# mrf89_v0_1.net
KiCad netlist of a schematic drawn in EAGLE
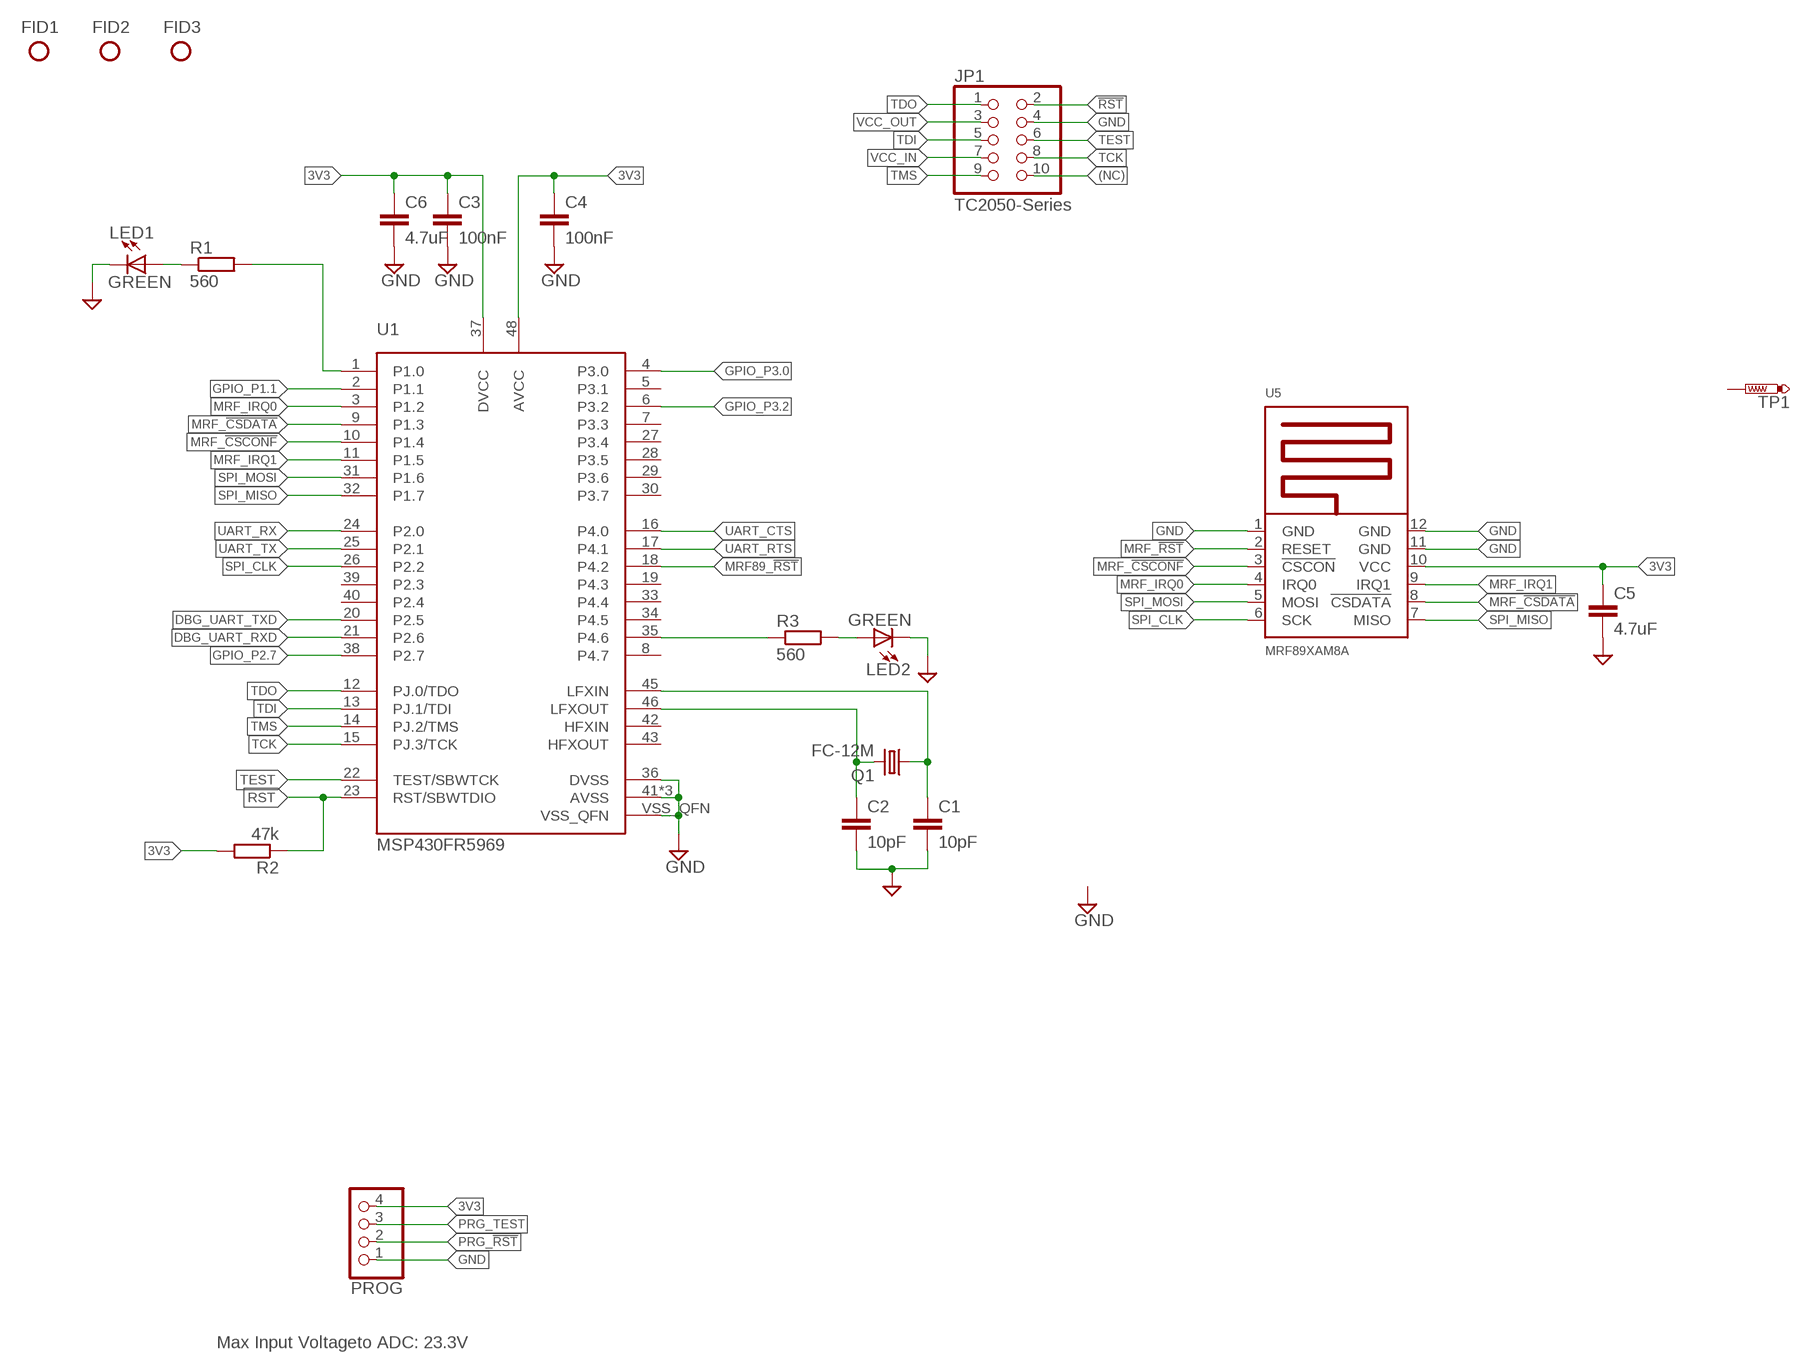
[diagram p0: schematic, sheet 1]

(export (version "E")
  (design (tool "Eeschema 10.0.6"))
  (components
    (comp (ref "C1")
      (value "10pF")
      (footprint "eagle-import:C0603")
      (libsource (lib "eagle-import") (part "C-EUC0603"))
    )
    (comp (ref "C2")
      (value "10pF")
      (footprint "eagle-import:C0603")
      (libsource (lib "eagle-import") (part "C-EUC0603"))
    )
    (comp (ref "C3")
      (value "100nF")
      (footprint "eagle-import:C0603")
      (libsource (lib "eagle-import") (part "C-EUC0603"))
    )
    (comp (ref "C4")
      (value "100nF")
      (footprint "eagle-import:C0603")
      (libsource (lib "eagle-import") (part "C-EUC0603"))
    )
    (comp (ref "C5")
      (value "4.7uF")
      (footprint "eagle-import:C0805")
      (libsource (lib "eagle-import") (part "C-EUC0805"))
    )
    (comp (ref "C6")
      (value "4.7uF")
      (footprint "eagle-import:C0805")
      (libsource (lib "eagle-import") (part "C-EUC0805"))
    )
    (comp (ref "FID1")
      (value "FIDUCIAL")
      (footprint "eagle-import:FIDUCIAL")
      (libsource (lib "eagle-import") (part "FIDUCIAL"))
    )
    (comp (ref "FID2")
      (value "FIDUCIAL")
      (footprint "eagle-import:FIDUCIAL")
      (libsource (lib "eagle-import") (part "FIDUCIAL"))
    )
    (comp (ref "FID3")
      (value "FIDUCIAL")
      (footprint "eagle-import:FIDUCIAL")
      (libsource (lib "eagle-import") (part "FIDUCIAL"))
    )
    (comp (ref "JP1")
      (value "TC2050-Series")
      (footprint "eagle-import:2X05")
      (libsource (lib "eagle-import") (part "PINHD-2X5"))
    )
    (comp (ref "LED1")
      (value "GREEN")
      (footprint "eagle-import:CHIP-LED0603")
      (libsource (lib "eagle-import") (part "LEDCHIP-LED0603"))
    )
    (comp (ref "LED2")
      (value "GREEN")
      (footprint "eagle-import:CHIP-LED0603")
      (libsource (lib "eagle-import") (part "LEDCHIP-LED0603"))
    )
    (comp (ref "PROG")
      (value "PINHD-1X4")
      (footprint "eagle-import:1X04")
      (libsource (lib "eagle-import") (part "PINHD-1X4"))
    )
    (comp (ref "Q1")
      (value "FC-12M")
      (footprint "eagle-import:FC-12M")
      (libsource (lib "eagle-import") (part "FC-12M"))
    )
    (comp (ref "R1")
      (value "560")
      (footprint "eagle-import:R0603")
      (libsource (lib "eagle-import") (part "R-EU_R0603"))
    )
    (comp (ref "R2")
      (value "47k")
      (footprint "eagle-import:R0603")
      (libsource (lib "eagle-import") (part "R-EU_R0603"))
    )
    (comp (ref "R3")
      (value "560")
      (footprint "eagle-import:R0603")
      (libsource (lib "eagle-import") (part "R-EU_R0603"))
    )
    (comp (ref "TP1")
      (value "PTR1PAD1-13")
      (footprint "eagle-import:P1-13")
      (libsource (lib "eagle-import") (part "PTR1PAD1-13"))
    )
    (comp (ref "U1")
      (value "MSP430FR5969")
      (footprint "eagle-import:S-PVQFN-N48")
      (libsource (lib "eagle-import") (part "MSP430FR5969"))
    )
    (comp (ref "U5")
      (value "MRF89XAM8A")
      (footprint "eagle-import:MRF89XAMXA")
      (libsource (lib "eagle-import") (part "MRF89XAM8A"))
    )
  )
  (nets
    (net (code "1") (name "(NC)") (class "Default")
      (node (ref "JP1") (pin "10") (pinfunction "10_10") (pintype "passive"))
    )
    (net (code "2") (name "/MRF89_~{RST}") (class "Default")
      (node (ref "U1") (pin "18") (pinfunction "P4.2_18") (pintype "bidirectional"))
    )
    (net (code "3") (name "/MRF_~{CSCONF}") (class "Default")
      (node (ref "U1") (pin "10") (pinfunction "P1.4_10") (pintype "bidirectional"))
      (node (ref "U5") (pin "3") (pinfunction "~{CSCON}_3") (pintype "input"))
    )
    (net (code "4") (name "/MRF_~{CSDATA}") (class "Default")
      (node (ref "U1") (pin "9") (pinfunction "P1.3_9") (pintype "bidirectional"))
      (node (ref "U5") (pin "8") (pinfunction "~{CSDATA}_8") (pintype "input"))
    )
    (net (code "5") (name "/MRF_~{RST}") (class "Default")
      (node (ref "U5") (pin "2") (pinfunction "RESET_2") (pintype "input"))
    )
    (net (code "6") (name "/PRG_~{RST}") (class "Default")
      (node (ref "PROG") (pin "2") (pinfunction "2_2") (pintype "passive"))
    )
    (net (code "7") (name "/~{RST}") (class "Default")
      (node (ref "JP1") (pin "2") (pinfunction "2_2") (pintype "passive"))
    )
    (net (code "8") (name "3V3") (class "Default")
      (node (ref "C3") (pin "1") (pinfunction "1_1") (pintype "passive"))
      (node (ref "C4") (pin "1") (pinfunction "1_1") (pintype "passive"))
      (node (ref "C5") (pin "1") (pinfunction "1_1") (pintype "passive"))
      (node (ref "C6") (pin "1") (pinfunction "1_1") (pintype "passive"))
      (node (ref "PROG") (pin "4") (pinfunction "4_4") (pintype "passive"))
      (node (ref "R2") (pin "2") (pinfunction "2_2") (pintype "passive"))
      (node (ref "U1") (pin "37") (pinfunction "DVCC_37") (pintype "bidirectional"))
      (node (ref "U1") (pin "48") (pinfunction "AVCC_48") (pintype "bidirectional"))
      (node (ref "U5") (pin "10") (pinfunction "VCC_10") (pintype "power_in"))
    )
    (net (code "9") (name "DBG_UART_RXD") (class "Default")
      (node (ref "U1") (pin "21") (pinfunction "P2.6_21") (pintype "bidirectional"))
    )
    (net (code "10") (name "DBG_UART_TXD") (class "Default")
      (node (ref "U1") (pin "20") (pinfunction "P2.5_20") (pintype "bidirectional"))
    )
    (net (code "11") (name "GND") (class "Default")
      (node (ref "C1") (pin "2") (pinfunction "2_2") (pintype "passive"))
      (node (ref "C2") (pin "2") (pinfunction "2_2") (pintype "passive"))
      (node (ref "C3") (pin "2") (pinfunction "2_2") (pintype "passive"))
      (node (ref "C4") (pin "2") (pinfunction "2_2") (pintype "passive"))
      (node (ref "C5") (pin "2") (pinfunction "2_2") (pintype "passive"))
      (node (ref "C6") (pin "2") (pinfunction "2_2") (pintype "passive"))
      (node (ref "JP1") (pin "4") (pinfunction "4_4") (pintype "passive"))
      (node (ref "LED1") (pin "C") (pinfunction "C_C") (pintype "passive"))
      (node (ref "LED2") (pin "C") (pinfunction "C_C") (pintype "passive"))
      (node (ref "PROG") (pin "1") (pinfunction "1_1") (pintype "passive"))
      (node (ref "U1") (pin "36") (pinfunction "DVSS_36") (pintype "bidirectional"))
      (node (ref "U1") (pin "41") (pinfunction "AVSS_41") (pintype "bidirectional"))
      (node (ref "U1") (pin "44") (pinfunction "AVSS_44") (pintype "bidirectional"))
      (node (ref "U1") (pin "47") (pinfunction "AVSS_47") (pintype "bidirectional"))
      (node (ref "U1") (pin "VSS_QFN") (pinfunction "VSS_QFN_VSS_QFN") (pintype "bidirectional"))
      (node (ref "U5") (pin "1") (pinfunction "GND_1") (pintype "power_in"))
      (node (ref "U5") (pin "11") (pinfunction "GND_11") (pintype "power_in"))
      (node (ref "U5") (pin "12") (pinfunction "GND_12") (pintype "power_in"))
    )
    (net (code "12") (name "GPIO_P1.1") (class "Default")
      (node (ref "U1") (pin "2") (pinfunction "P1.1_2") (pintype "bidirectional"))
    )
    (net (code "13") (name "GPIO_P2.7") (class "Default")
      (node (ref "U1") (pin "38") (pinfunction "P2.7_38") (pintype "bidirectional"))
    )
    (net (code "14") (name "GPIO_P3.0") (class "Default")
      (node (ref "U1") (pin "4") (pinfunction "P3.0_4") (pintype "bidirectional"))
    )
    (net (code "15") (name "GPIO_P3.2") (class "Default")
      (node (ref "U1") (pin "6") (pinfunction "P3.2_6") (pintype "bidirectional"))
    )
    (net (code "16") (name "MRF_IRQ0") (class "Default")
      (node (ref "U1") (pin "3") (pinfunction "P1.2_3") (pintype "bidirectional"))
      (node (ref "U5") (pin "4") (pinfunction "IRQ0_4") (pintype "output"))
    )
    (net (code "17") (name "MRF_IRQ1") (class "Default")
      (node (ref "U1") (pin "11") (pinfunction "P1.5_11") (pintype "bidirectional"))
      (node (ref "U5") (pin "9") (pinfunction "IRQ1_9") (pintype "output"))
    )
    (net (code "18") (name "Net-(LED1-PadA)") (class "Default")
      (node (ref "LED1") (pin "A") (pinfunction "A_A") (pintype "passive"))
      (node (ref "R1") (pin "1") (pinfunction "1_1") (pintype "passive"))
    )
    (net (code "19") (name "Net-(LED2-PadA)") (class "Default")
      (node (ref "LED2") (pin "A") (pinfunction "A_A") (pintype "passive"))
      (node (ref "R3") (pin "2") (pinfunction "2_2") (pintype "passive"))
    )
    (net (code "20") (name "Net-(U1-LFXIN)") (class "Default")
      (node (ref "C1") (pin "1") (pinfunction "1_1") (pintype "passive"))
      (node (ref "Q1") (pin "1") (pinfunction "1_1") (pintype "passive"))
      (node (ref "U1") (pin "45") (pinfunction "LFXIN_45") (pintype "bidirectional"))
    )
    (net (code "21") (name "Net-(U1-LFXOUT)") (class "Default")
      (node (ref "C2") (pin "1") (pinfunction "1_1") (pintype "passive"))
      (node (ref "Q1") (pin "2") (pinfunction "2_2") (pintype "passive"))
      (node (ref "U1") (pin "46") (pinfunction "LFXOUT_46") (pintype "bidirectional"))
    )
    (net (code "22") (name "Net-(U1-P1.0)") (class "Default")
      (node (ref "R1") (pin "2") (pinfunction "2_2") (pintype "passive"))
      (node (ref "U1") (pin "1") (pinfunction "P1.0_1") (pintype "bidirectional"))
    )
    (net (code "23") (name "Net-(U1-P4.6)") (class "Default")
      (node (ref "R3") (pin "1") (pinfunction "1_1") (pintype "passive"))
      (node (ref "U1") (pin "35") (pinfunction "P4.6_35") (pintype "bidirectional"))
    )
    (net (code "24") (name "PRG_TEST") (class "Default")
      (node (ref "PROG") (pin "3") (pinfunction "3_3") (pintype "passive"))
    )
    (net (code "25") (name "RST") (class "Default")
      (node (ref "R2") (pin "1") (pinfunction "1_1") (pintype "passive"))
      (node (ref "U1") (pin "23") (pinfunction "RST/SBWTDIO_23") (pintype "bidirectional"))
    )
    (net (code "26") (name "SPI_CLK") (class "Default")
      (node (ref "U1") (pin "26") (pinfunction "P2.2_26") (pintype "bidirectional"))
      (node (ref "U5") (pin "6") (pinfunction "SCK_6") (pintype "input"))
    )
    (net (code "27") (name "SPI_MISO") (class "Default")
      (node (ref "U1") (pin "32") (pinfunction "P1.7_32") (pintype "bidirectional"))
      (node (ref "U5") (pin "7") (pinfunction "MISO_7") (pintype "output"))
    )
    (net (code "28") (name "SPI_MOSI") (class "Default")
      (node (ref "U1") (pin "31") (pinfunction "P1.6_31") (pintype "bidirectional"))
      (node (ref "U5") (pin "5") (pinfunction "MOSI_5") (pintype "input"))
    )
    (net (code "29") (name "TCK") (class "Default")
      (node (ref "JP1") (pin "8") (pinfunction "8_8") (pintype "passive"))
      (node (ref "U1") (pin "15") (pinfunction "PJ.3/TCK_15") (pintype "bidirectional"))
    )
    (net (code "30") (name "TDI") (class "Default")
      (node (ref "JP1") (pin "5") (pinfunction "5_5") (pintype "passive"))
      (node (ref "U1") (pin "13") (pinfunction "PJ.1/TDI_13") (pintype "bidirectional"))
    )
    (net (code "31") (name "TDO") (class "Default")
      (node (ref "JP1") (pin "1") (pinfunction "1_1") (pintype "passive"))
      (node (ref "U1") (pin "12") (pinfunction "PJ.0/TDO_12") (pintype "bidirectional"))
    )
    (net (code "32") (name "TEST") (class "Default")
      (node (ref "JP1") (pin "6") (pinfunction "6_6") (pintype "passive"))
      (node (ref "U1") (pin "22") (pinfunction "TEST/SBWTCK_22") (pintype "bidirectional"))
    )
    (net (code "33") (name "TMS") (class "Default")
      (node (ref "JP1") (pin "9") (pinfunction "9_9") (pintype "passive"))
      (node (ref "U1") (pin "14") (pinfunction "PJ.2/TMS_14") (pintype "bidirectional"))
    )
    (net (code "34") (name "UART_CTS") (class "Default")
      (node (ref "U1") (pin "16") (pinfunction "P4.0_16") (pintype "bidirectional"))
    )
    (net (code "35") (name "UART_RTS") (class "Default")
      (node (ref "U1") (pin "17") (pinfunction "P4.1_17") (pintype "bidirectional"))
    )
    (net (code "36") (name "UART_RX") (class "Default")
      (node (ref "U1") (pin "24") (pinfunction "P2.0_24") (pintype "bidirectional"))
    )
    (net (code "37") (name "UART_TX") (class "Default")
      (node (ref "U1") (pin "25") (pinfunction "P2.1_25") (pintype "bidirectional"))
    )
    (net (code "38") (name "VCC_IN") (class "Default")
      (node (ref "JP1") (pin "7") (pinfunction "7_7") (pintype "passive"))
    )
    (net (code "39") (name "VCC_OUT") (class "Default")
      (node (ref "JP1") (pin "3") (pinfunction "3_3") (pintype "passive"))
    )
    (net (code "40") (name "unconnected-(TP1-PadTP)") (class "Default")
      (node (ref "TP1") (pin "TP") (pinfunction "TP_TP") (pintype "input"))
    )
    (net (code "41") (name "unconnected-(U1-HFXIN-Pad42)") (class "Default")
      (node (ref "U1") (pin "42") (pinfunction "HFXIN_42") (pintype "bidirectional"))
    )
    (net (code "42") (name "unconnected-(U1-HFXOUT-Pad43)") (class "Default")
      (node (ref "U1") (pin "43") (pinfunction "HFXOUT_43") (pintype "bidirectional"))
    )
    (net (code "43") (name "unconnected-(U1-P2.3-Pad39)") (class "Default")
      (node (ref "U1") (pin "39") (pinfunction "P2.3_39") (pintype "bidirectional"))
    )
    (net (code "44") (name "unconnected-(U1-P2.4-Pad40)") (class "Default")
      (node (ref "U1") (pin "40") (pinfunction "P2.4_40") (pintype "bidirectional"))
    )
    (net (code "45") (name "unconnected-(U1-P3.1-Pad5)") (class "Default")
      (node (ref "U1") (pin "5") (pinfunction "P3.1_5") (pintype "bidirectional"))
    )
    (net (code "46") (name "unconnected-(U1-P3.3-Pad7)") (class "Default")
      (node (ref "U1") (pin "7") (pinfunction "P3.3_7") (pintype "bidirectional"))
    )
    (net (code "47") (name "unconnected-(U1-P3.4-Pad27)") (class "Default")
      (node (ref "U1") (pin "27") (pinfunction "P3.4_27") (pintype "bidirectional"))
    )
    (net (code "48") (name "unconnected-(U1-P3.5-Pad28)") (class "Default")
      (node (ref "U1") (pin "28") (pinfunction "P3.5_28") (pintype "bidirectional"))
    )
    (net (code "49") (name "unconnected-(U1-P3.6-Pad29)") (class "Default")
      (node (ref "U1") (pin "29") (pinfunction "P3.6_29") (pintype "bidirectional"))
    )
    (net (code "50") (name "unconnected-(U1-P3.7-Pad30)") (class "Default")
      (node (ref "U1") (pin "30") (pinfunction "P3.7_30") (pintype "bidirectional"))
    )
    (net (code "51") (name "unconnected-(U1-P4.3-Pad19)") (class "Default")
      (node (ref "U1") (pin "19") (pinfunction "P4.3_19") (pintype "bidirectional"))
    )
    (net (code "52") (name "unconnected-(U1-P4.4-Pad33)") (class "Default")
      (node (ref "U1") (pin "33") (pinfunction "P4.4_33") (pintype "bidirectional"))
    )
    (net (code "53") (name "unconnected-(U1-P4.5-Pad34)") (class "Default")
      (node (ref "U1") (pin "34") (pinfunction "P4.5_34") (pintype "bidirectional"))
    )
    (net (code "54") (name "unconnected-(U1-P4.7-Pad8)") (class "Default")
      (node (ref "U1") (pin "8") (pinfunction "P4.7_8") (pintype "bidirectional"))
    )
  )
)
